# Reed_Switch_Schematics.net
KiCad netlist of a schematic drawn in EAGLE
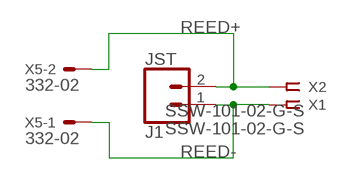
[diagram p0: schematic, sheet 1]

(export (version "E")
  (design (tool "Eeschema 10.0.6"))
  (components
    (comp (ref "J1")
      (value "JST")
      (footprint "eagle-import:JST-2-SMD")
      (libsource (lib "eagle-import") (part "CONN_02-JST-2MM-SMT"))
    )
    (comp (ref "X1")
      (value "SSW-101-02-G-S")
      (footprint "eagle-import:SSW-101-02-G-S")
      (fields (field (name "MF") "Samtec Inc."))
      (libsource (lib "eagle-import") (part "SSW-101-02-G-S"))
    )
    (comp (ref "X2")
      (value "SSW-101-02-G-S")
      (footprint "eagle-import:SSW-101-02-G-S")
      (fields (field (name "MF") "Samtec Inc."))
      (libsource (lib "eagle-import") (part "SSW-101-02-G-S"))
    )
    (comp (ref "X5")
      (value "332-02")
      (footprint "eagle-import:332-02")
      (libsource (lib "eagle-import") (part "332-02"))
    )
  )
  (nets
    (net (code "1") (name "/REED+") (class "Default")
      (node (ref "J1") (pin "2") (pinfunction "1_2") (pintype "passive"))
      (node (ref "X2") (pin "1") (pinfunction "1_1") (pintype "passive"))
      (node (ref "X5") (pin "2") (pinfunction "S_2") (pintype "passive"))
    )
    (net (code "2") (name "/REED-") (class "Default")
      (node (ref "J1") (pin "1") (pinfunction "2_1") (pintype "passive"))
      (node (ref "X1") (pin "1") (pinfunction "1_1") (pintype "passive"))
      (node (ref "X5") (pin "1") (pinfunction "S_1") (pintype "passive"))
    )
  )
)
